# pic.net
KiCad netlist of a schematic drawn in Altium Designer
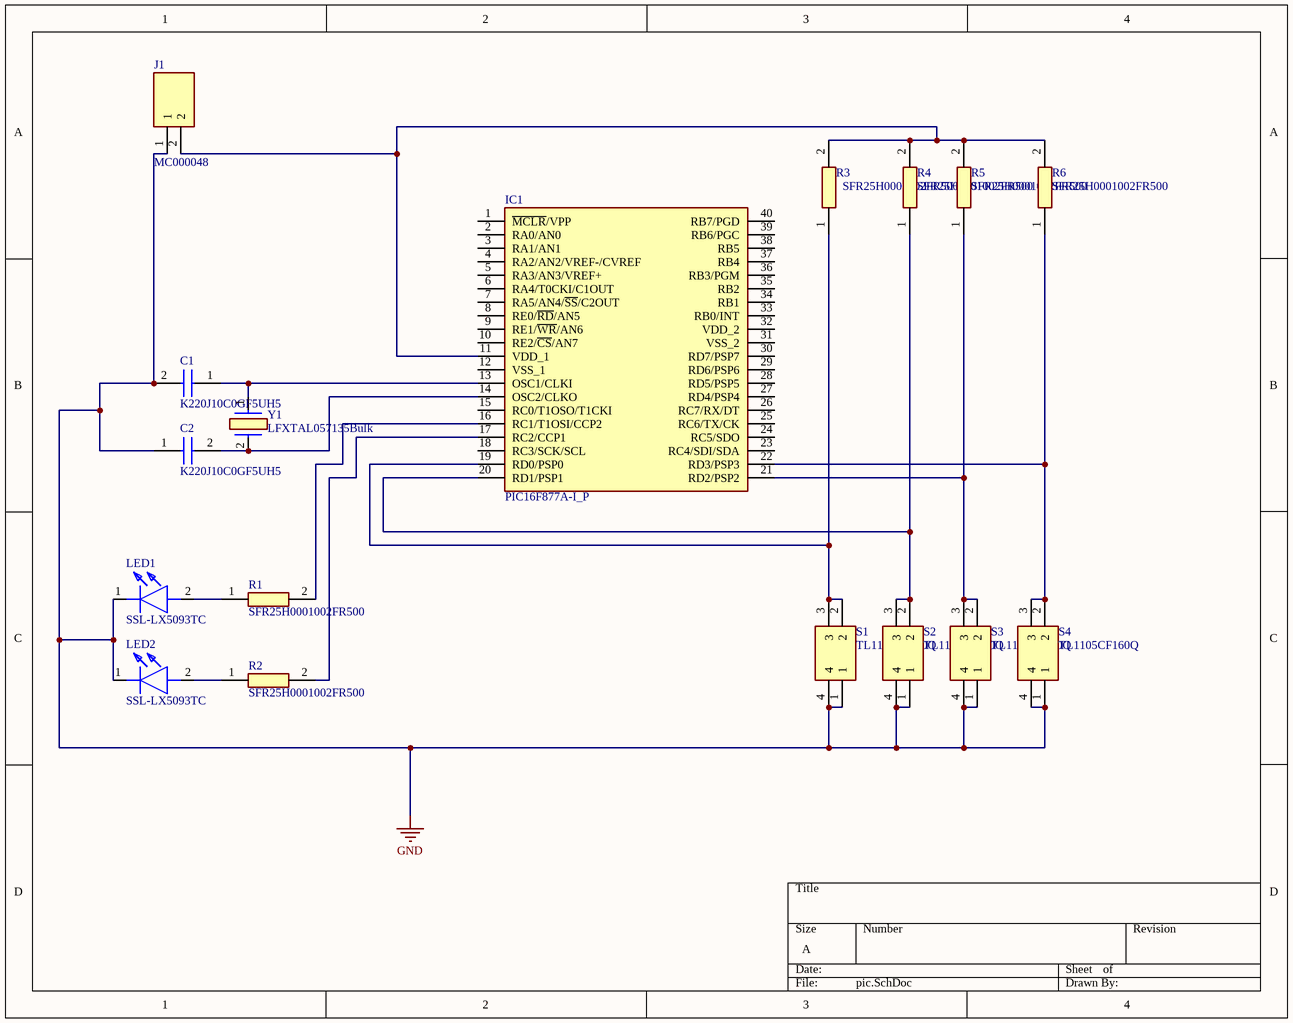
[diagram p0: pic.SchDoc]

(export (version "E")
  (design (tool "Eeschema 10.0.6"))
  (components
    (comp (ref "C1")
      (value "K220J10C0GF5UH5")
      (footprint "SamacSys:K220J10C0GF5UH5")
      (description "Capacitor")
      (fields (field (name "MOUSER PART NUMBER") "594-K220J10C0GF5UH5"))
      (libsource (lib "*") (part "K220J10C0GF5UH5"))
    )
    (comp (ref "C2")
      (value "K220J10C0GF5UH5")
      (footprint "SamacSys:K220J10C0GF5UH5")
      (description "Capacitor")
      (fields (field (name "MOUSER PART NUMBER") "594-K220J10C0GF5UH5"))
      (libsource (lib "SamacSys") (part "K220J10C0GF5UH5"))
    )
    (comp (ref "IC1")
      (value "PIC16F877A-I_P")
      (footprint "SamacSys:DIP1550W56P254L5219H483Q40N")
      (description "Integrated Circuit")
      (fields
        (field (name "MANUFACTURER_PART_NUMBER") "PIC16F877A-I/P")
        (field (name "MOUSER PART NUMBER") "579-PIC16F877A-I/P")
      )
      (libsource (lib "*") (part "PIC16F877A-I_P"))
    )
    (comp (ref "J1")
      (value "MC000048")
      (footprint "SamacSys:MC000048")
      (description "Connector")
      (libsource (lib "*") (part "MC000048"))
    )
    (comp (ref "LED1")
      (value "SSL-LX5093TC")
      (footprint "SamacSys:SSL-LX5093SGC/B")
      (description "LED")
      (fields (field (name "MOUSER PART NUMBER") "696-SSL-LX5093TC"))
      (libsource (lib "*") (part "SSL-LX5093TC"))
    )
    (comp (ref "LED2")
      (value "SSL-LX5093TC")
      (footprint "SamacSys:SSL-LX5093SGC/B")
      (description "LED")
      (fields (field (name "MOUSER PART NUMBER") "696-SSL-LX5093TC"))
      (libsource (lib "SamacSys") (part "SSL-LX5093TC"))
    )
    (comp (ref "R1")
      (value "SFR25H0001002FR500")
      (footprint "SamacSys:RESAD1750W63L750D250")
      (description "Resistor")
      (fields (field (name "MOUSER PART NUMBER") "594-5053HD10K00F"))
      (libsource (lib "") (part "SFR25H0001002FR500_1"))
    )
    (comp (ref "R2")
      (value "SFR25H0001002FR500")
      (footprint "SamacSys:RESAD1750W63L750D250")
      (description "Resistor")
      (fields (field (name "MOUSER PART NUMBER") "594-5053HD10K00F"))
      (libsource (lib "") (part "SFR25H0001002FR500_1"))
    )
    (comp (ref "R3")
      (value "SFR25H0001002FR500")
      (footprint "SamacSys:RESAD1750W63L750D250")
      (description "Resistor")
      (fields (field (name "MOUSER PART NUMBER") "594-5053HD10K00F"))
      (libsource (lib "*") (part "SFR25H0001002FR500"))
    )
    (comp (ref "R4")
      (value "SFR25H0001002FR500")
      (footprint "SamacSys:RESAD1750W63L750D250")
      (description "Resistor")
      (fields (field (name "MOUSER PART NUMBER") "594-5053HD10K00F"))
      (libsource (lib "SamacSys") (part "SFR25H0001002FR500"))
    )
    (comp (ref "R5")
      (value "SFR25H0001002FR500")
      (footprint "SamacSys:RESAD1750W63L750D250")
      (description "Resistor")
      (fields (field (name "MOUSER PART NUMBER") "594-5053HD10K00F"))
      (libsource (lib "SamacSys") (part "SFR25H0001002FR500"))
    )
    (comp (ref "R6")
      (value "SFR25H0001002FR500")
      (footprint "SamacSys:RESAD1750W63L750D250")
      (description "Resistor")
      (fields (field (name "MOUSER PART NUMBER") "594-5053HD10K00F"))
      (libsource (lib "SamacSys") (part "SFR25H0001002FR500"))
    )
    (comp (ref "S1")
      (value "TL1105CF160Q")
      (footprint "SamacSys:TL1105CF160Q")
      (description "Switch")
      (fields (field (name "MOUSER PART NUMBER") "612-TL1105C"))
      (libsource (lib "*") (part "TL1105CF160Q"))
    )
    (comp (ref "S2")
      (value "TL1105CF160Q")
      (footprint "SamacSys:TL1105CF160Q")
      (description "Switch")
      (fields (field (name "MOUSER PART NUMBER") "612-TL1105C"))
      (libsource (lib "SamacSys") (part "TL1105CF160Q"))
    )
    (comp (ref "S3")
      (value "TL1105CF160Q")
      (footprint "SamacSys:TL1105CF160Q")
      (description "Switch")
      (fields (field (name "MOUSER PART NUMBER") "612-TL1105C"))
      (libsource (lib "SamacSys") (part "TL1105CF160Q"))
    )
    (comp (ref "S4")
      (value "TL1105CF160Q")
      (footprint "SamacSys:TL1105CF160Q")
      (description "Switch")
      (fields (field (name "MOUSER PART NUMBER") "612-TL1105C"))
      (libsource (lib "SamacSys") (part "TL1105CF160Q"))
    )
    (comp (ref "Y1")
      (value "LFXTAL057135Bulk")
      (footprint "SamacSys:LFXTAL057135Bulk")
      (description "Crystal or Oscillator")
      (fields (field (name "MOUSER PART NUMBER") "449-LFXTAL057135BULK"))
      (libsource (lib "*") (part "LFXTAL057135Bulk"))
    )
  )
  (nets
    (net (code "1") (name "GND") (class "Default")
      (node (ref "C1") (pin "2") (pinfunction "2_2") (pintype "passive"))
      (node (ref "C2") (pin "1") (pinfunction "1_1") (pintype "passive"))
      (node (ref "J1") (pin "1") (pinfunction "1_1") (pintype "passive"))
      (node (ref "LED1") (pin "1") (pinfunction "K_1") (pintype "passive"))
      (node (ref "LED2") (pin "1") (pinfunction "K_1") (pintype "passive"))
      (node (ref "S1") (pin "1") (pinfunction "1_1") (pintype "passive"))
      (node (ref "S1") (pin "4") (pinfunction "4_4") (pintype "passive"))
      (node (ref "S2") (pin "1") (pinfunction "1_1") (pintype "passive"))
      (node (ref "S2") (pin "4") (pinfunction "4_4") (pintype "passive"))
      (node (ref "S3") (pin "1") (pinfunction "1_1") (pintype "passive"))
      (node (ref "S3") (pin "4") (pinfunction "4_4") (pintype "passive"))
      (node (ref "S4") (pin "1") (pinfunction "1_1") (pintype "passive"))
      (node (ref "S4") (pin "4") (pinfunction "4_4") (pintype "passive"))
    )
    (net (code "2") (name "Net-(IC1-OSC1{slash}CLKI)") (class "Default")
      (node (ref "C1") (pin "1") (pinfunction "1_1") (pintype "passive"))
      (node (ref "IC1") (pin "13") (pinfunction "OSC1/CLKI_13") (pintype "passive"))
      (node (ref "Y1") (pin "1") (pinfunction "1_1") (pintype "passive"))
    )
    (net (code "3") (name "Net-(IC1-OSC2{slash}CLKO)") (class "Default")
      (node (ref "C2") (pin "2") (pinfunction "2_2") (pintype "passive"))
      (node (ref "IC1") (pin "14") (pinfunction "OSC2/CLKO_14") (pintype "passive"))
      (node (ref "Y1") (pin "2") (pinfunction "2_2") (pintype "passive"))
    )
    (net (code "4") (name "Net-(IC1-RC1{slash}T1OSI{slash}CCP2)") (class "Default")
      (node (ref "IC1") (pin "16") (pinfunction "RC1/T1OSI/CCP2_16") (pintype "passive"))
      (node (ref "R1") (pin "2") (pinfunction "2_2") (pintype "passive"))
    )
    (net (code "5") (name "Net-(IC1-RC2{slash}CCP1)") (class "Default")
      (node (ref "IC1") (pin "17") (pinfunction "RC2/CCP1_17") (pintype "passive"))
      (node (ref "R2") (pin "2") (pinfunction "2_2") (pintype "passive"))
    )
    (net (code "6") (name "Net-(IC1-RD0{slash}PSP0)") (class "Default")
      (node (ref "IC1") (pin "19") (pinfunction "RD0/PSP0_19") (pintype "passive"))
      (node (ref "R3") (pin "1") (pinfunction "1_1") (pintype "passive"))
      (node (ref "S1") (pin "2") (pinfunction "2_2") (pintype "passive"))
      (node (ref "S1") (pin "3") (pinfunction "3_3") (pintype "passive"))
    )
    (net (code "7") (name "Net-(IC1-RD1{slash}PSP1)") (class "Default")
      (node (ref "IC1") (pin "20") (pinfunction "RD1/PSP1_20") (pintype "passive"))
      (node (ref "R4") (pin "1") (pinfunction "1_1") (pintype "passive"))
      (node (ref "S2") (pin "2") (pinfunction "2_2") (pintype "passive"))
      (node (ref "S2") (pin "3") (pinfunction "3_3") (pintype "passive"))
    )
    (net (code "8") (name "Net-(IC1-RD2{slash}PSP2)") (class "Default")
      (node (ref "IC1") (pin "21") (pinfunction "RD2/PSP2_21") (pintype "passive"))
      (node (ref "R5") (pin "1") (pinfunction "1_1") (pintype "passive"))
      (node (ref "S3") (pin "2") (pinfunction "2_2") (pintype "passive"))
      (node (ref "S3") (pin "3") (pinfunction "3_3") (pintype "passive"))
    )
    (net (code "9") (name "Net-(IC1-RD3{slash}PSP3)") (class "Default")
      (node (ref "IC1") (pin "22") (pinfunction "RD3/PSP3_22") (pintype "passive"))
      (node (ref "R6") (pin "1") (pinfunction "1_1") (pintype "passive"))
      (node (ref "S4") (pin "2") (pinfunction "2_2") (pintype "passive"))
      (node (ref "S4") (pin "3") (pinfunction "3_3") (pintype "passive"))
    )
    (net (code "10") (name "Net-(IC1-VDD_1)") (class "Default")
      (node (ref "IC1") (pin "11") (pinfunction "VDD_1_11") (pintype "passive"))
      (node (ref "J1") (pin "2") (pinfunction "2_2") (pintype "passive"))
      (node (ref "R3") (pin "2") (pinfunction "2_2") (pintype "passive"))
      (node (ref "R4") (pin "2") (pinfunction "2_2") (pintype "passive"))
      (node (ref "R5") (pin "2") (pinfunction "2_2") (pintype "passive"))
      (node (ref "R6") (pin "2") (pinfunction "2_2") (pintype "passive"))
    )
    (net (code "11") (name "Net-(LED1-A)") (class "Default")
      (node (ref "LED1") (pin "2") (pinfunction "A_2") (pintype "passive"))
      (node (ref "R1") (pin "1") (pinfunction "1_1") (pintype "passive"))
    )
    (net (code "12") (name "Net-(LED2-A)") (class "Default")
      (node (ref "LED2") (pin "2") (pinfunction "A_2") (pintype "passive"))
      (node (ref "R2") (pin "1") (pinfunction "1_1") (pintype "passive"))
    )
    (net (code "13") (name "unconnected-(IC1-RA0{slash}AN0-Pad2)") (class "Default")
      (node (ref "IC1") (pin "2") (pinfunction "RA0/AN0_2") (pintype "passive"))
    )
    (net (code "14") (name "unconnected-(IC1-RA1{slash}AN1-Pad3)") (class "Default")
      (node (ref "IC1") (pin "3") (pinfunction "RA1/AN1_3") (pintype "passive"))
    )
    (net (code "15") (name "unconnected-(IC1-RA2{slash}AN2{slash}VREF-{slash}CVREF-Pad4)") (class "Default")
      (node (ref "IC1") (pin "4") (pinfunction "RA2/AN2/VREF-/CVREF_4") (pintype "passive"))
    )
    (net (code "16") (name "unconnected-(IC1-RA3{slash}AN3{slash}VREF+-Pad5)") (class "Default")
      (node (ref "IC1") (pin "5") (pinfunction "RA3/AN3/VREF+_5") (pintype "passive"))
    )
    (net (code "17") (name "unconnected-(IC1-RA4{slash}T0CKI{slash}C1OUT-Pad6)") (class "Default")
      (node (ref "IC1") (pin "6") (pinfunction "RA4/T0CKI/C1OUT_6") (pintype "passive"))
    )
    (net (code "18") (name "unconnected-(IC1-RA5{slash}AN4{slash}~{SS}{slash}C2OUT-Pad7)") (class "Default")
      (node (ref "IC1") (pin "7") (pinfunction "RA5/AN4/~{SS}/C2OUT_7") (pintype "passive"))
    )
    (net (code "19") (name "unconnected-(IC1-RB0{slash}INT-Pad33)") (class "Default")
      (node (ref "IC1") (pin "33") (pinfunction "RB0/INT_33") (pintype "passive"))
    )
    (net (code "20") (name "unconnected-(IC1-RB1-Pad34)") (class "Default")
      (node (ref "IC1") (pin "34") (pinfunction "RB1_34") (pintype "passive"))
    )
    (net (code "21") (name "unconnected-(IC1-RB2-Pad35)") (class "Default")
      (node (ref "IC1") (pin "35") (pinfunction "RB2_35") (pintype "passive"))
    )
    (net (code "22") (name "unconnected-(IC1-RB3{slash}PGM-Pad36)") (class "Default")
      (node (ref "IC1") (pin "36") (pinfunction "RB3/PGM_36") (pintype "passive"))
    )
    (net (code "23") (name "unconnected-(IC1-RB4-Pad37)") (class "Default")
      (node (ref "IC1") (pin "37") (pinfunction "RB4_37") (pintype "passive"))
    )
    (net (code "24") (name "unconnected-(IC1-RB5-Pad38)") (class "Default")
      (node (ref "IC1") (pin "38") (pinfunction "RB5_38") (pintype "passive"))
    )
    (net (code "25") (name "unconnected-(IC1-RB6{slash}PGC-Pad39)") (class "Default")
      (node (ref "IC1") (pin "39") (pinfunction "RB6/PGC_39") (pintype "passive"))
    )
    (net (code "26") (name "unconnected-(IC1-RB7{slash}PGD-Pad40)") (class "Default")
      (node (ref "IC1") (pin "40") (pinfunction "RB7/PGD_40") (pintype "passive"))
    )
    (net (code "27") (name "unconnected-(IC1-RC0{slash}T1OSO{slash}T1CKI-Pad15)") (class "Default")
      (node (ref "IC1") (pin "15") (pinfunction "RC0/T1OSO/T1CKI_15") (pintype "passive"))
    )
    (net (code "28") (name "unconnected-(IC1-RC3{slash}SCK{slash}SCL-Pad18)") (class "Default")
      (node (ref "IC1") (pin "18") (pinfunction "RC3/SCK/SCL_18") (pintype "passive"))
    )
    (net (code "29") (name "unconnected-(IC1-RC4{slash}SDI{slash}SDA-Pad23)") (class "Default")
      (node (ref "IC1") (pin "23") (pinfunction "RC4/SDI/SDA_23") (pintype "passive"))
    )
    (net (code "30") (name "unconnected-(IC1-RC5{slash}SDO-Pad24)") (class "Default")
      (node (ref "IC1") (pin "24") (pinfunction "RC5/SDO_24") (pintype "passive"))
    )
    (net (code "31") (name "unconnected-(IC1-RC6{slash}TX{slash}CK-Pad25)") (class "Default")
      (node (ref "IC1") (pin "25") (pinfunction "RC6/TX/CK_25") (pintype "passive"))
    )
    (net (code "32") (name "unconnected-(IC1-RC7{slash}RX{slash}DT-Pad26)") (class "Default")
      (node (ref "IC1") (pin "26") (pinfunction "RC7/RX/DT_26") (pintype "passive"))
    )
    (net (code "33") (name "unconnected-(IC1-RD4{slash}PSP4-Pad27)") (class "Default")
      (node (ref "IC1") (pin "27") (pinfunction "RD4/PSP4_27") (pintype "passive"))
    )
    (net (code "34") (name "unconnected-(IC1-RD5{slash}PSP5-Pad28)") (class "Default")
      (node (ref "IC1") (pin "28") (pinfunction "RD5/PSP5_28") (pintype "passive"))
    )
    (net (code "35") (name "unconnected-(IC1-RD6{slash}PSP6-Pad29)") (class "Default")
      (node (ref "IC1") (pin "29") (pinfunction "RD6/PSP6_29") (pintype "passive"))
    )
    (net (code "36") (name "unconnected-(IC1-RD7{slash}PSP7-Pad30)") (class "Default")
      (node (ref "IC1") (pin "30") (pinfunction "RD7/PSP7_30") (pintype "passive"))
    )
    (net (code "37") (name "unconnected-(IC1-RE0{slash}~{RD}{slash}AN5-Pad8)") (class "Default")
      (node (ref "IC1") (pin "8") (pinfunction "RE0/~{RD}/AN5_8") (pintype "passive"))
    )
    (net (code "38") (name "unconnected-(IC1-RE1{slash}~{WR}{slash}AN6-Pad9)") (class "Default")
      (node (ref "IC1") (pin "9") (pinfunction "RE1/~{WR}/AN6_9") (pintype "passive"))
    )
    (net (code "39") (name "unconnected-(IC1-RE2{slash}~{CS}{slash}AN7-Pad10)") (class "Default")
      (node (ref "IC1") (pin "10") (pinfunction "RE2/~{CS}/AN7_10") (pintype "passive"))
    )
    (net (code "40") (name "unconnected-(IC1-VDD_2-Pad32)") (class "Default")
      (node (ref "IC1") (pin "32") (pinfunction "VDD_2_32") (pintype "passive"))
    )
    (net (code "41") (name "unconnected-(IC1-VSS_1-Pad12)") (class "Default")
      (node (ref "IC1") (pin "12") (pinfunction "VSS_1_12") (pintype "passive"))
    )
    (net (code "42") (name "unconnected-(IC1-VSS_2-Pad31)") (class "Default")
      (node (ref "IC1") (pin "31") (pinfunction "VSS_2_31") (pintype "passive"))
    )
    (net (code "43") (name "unconnected-(IC1-~{MCLR}{slash}VPP-Pad1)") (class "Default")
      (node (ref "IC1") (pin "1") (pinfunction "~{MCLR}/VPP_1") (pintype "passive"))
    )
  )
)
